# HixButton.net
KiCad netlist of a schematic drawn in EAGLE
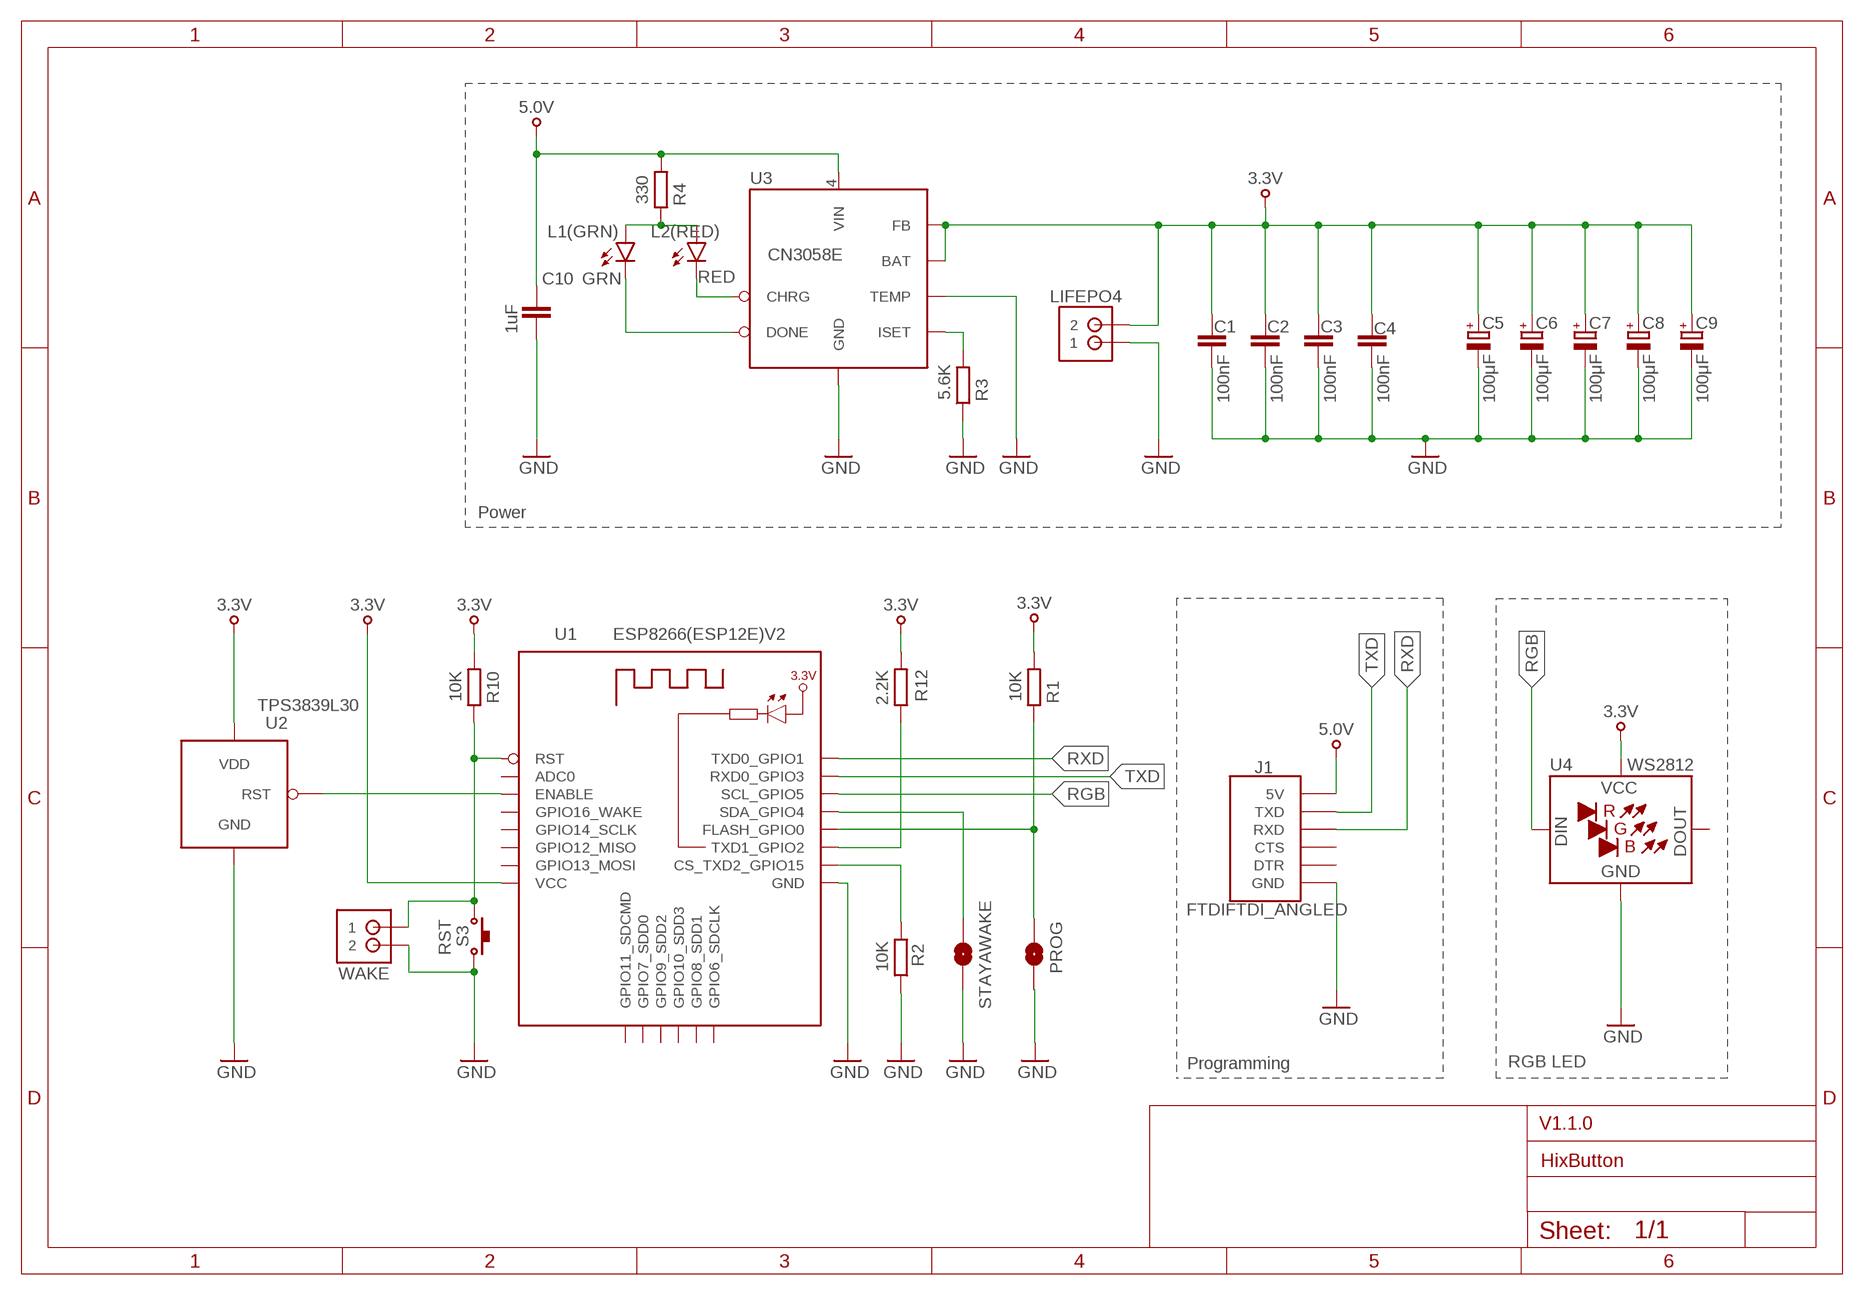
[diagram p0: schematic, sheet 1]

(export (version "E")
  (design (tool "Eeschema 10.0.6"))
  (components
    (comp (ref "C1")
      (value "100nF")
      (footprint "eagle-import:C1206")
      (libsource (lib "eagle-import") (part "C-EUC1206"))
    )
    (comp (ref "C2")
      (value "100nF")
      (footprint "eagle-import:C1206")
      (libsource (lib "eagle-import") (part "C-EUC1206"))
    )
    (comp (ref "C3")
      (value "100nF")
      (footprint "eagle-import:C1206")
      (libsource (lib "eagle-import") (part "C-EUC1206"))
    )
    (comp (ref "C4")
      (value "100nF")
      (footprint "eagle-import:C1206")
      (libsource (lib "eagle-import") (part "C-EUC1206"))
    )
    (comp (ref "C5")
      (value "100μF")
      (footprint "eagle-import:SMC_A")
      (libsource (lib "eagle-import") (part "CPOL-EUSMCA"))
    )
    (comp (ref "C6")
      (value "100μF")
      (footprint "eagle-import:SMC_A")
      (libsource (lib "eagle-import") (part "CPOL-EUSMCA"))
    )
    (comp (ref "C7")
      (value "100μF")
      (footprint "eagle-import:SMC_A")
      (libsource (lib "eagle-import") (part "CPOL-EUSMCA"))
    )
    (comp (ref "C8")
      (value "100μF")
      (footprint "eagle-import:SMC_A")
      (libsource (lib "eagle-import") (part "CPOL-EUSMCA"))
    )
    (comp (ref "C9")
      (value "100μF")
      (footprint "eagle-import:SMC_A")
      (libsource (lib "eagle-import") (part "CPOL-EUSMCA"))
    )
    (comp (ref "C10")
      (value "1uF")
      (footprint "eagle-import:C1206")
      (libsource (lib "eagle-import") (part "C-EUC1206"))
    )
    (comp (ref "J1")
      (value "FTDIFTDI_ANGLED")
      (footprint "eagle-import:FTDI_ANGLED")
      (libsource (lib "eagle-import") (part "FTDIFTDI_ANGLED"))
    )
    (comp (ref "L1(GRN)")
      (value "GRN")
      (footprint "eagle-import:CHIPLED_1206")
      (libsource (lib "eagle-import") (part "LEDCHIPLED_1206"))
    )
    (comp (ref "L2(RED)")
      (value "RED")
      (footprint "eagle-import:CHIPLED_1206")
      (libsource (lib "eagle-import") (part "LEDCHIPLED_1206"))
    )
    (comp (ref "LIFEPO4")
      (value "XH2P")
      (footprint "eagle-import:XH2P")
      (libsource (lib "eagle-import") (part "XH2P"))
    )
    (comp (ref "PROG")
      (value "SJ")
      (footprint "eagle-import:SJ")
      (fields (field (name "SPICEPREFIX") "B"))
      (libsource (lib "eagle-import") (part "SJ"))
    )
    (comp (ref "R1")
      (value "10K")
      (footprint "eagle-import:R1206")
      (libsource (lib "eagle-import") (part "R-EU_R1206"))
    )
    (comp (ref "R2")
      (value "10K")
      (footprint "eagle-import:R1206")
      (libsource (lib "eagle-import") (part "R-EU_R1206"))
    )
    (comp (ref "R3")
      (value "5.6K")
      (footprint "eagle-import:R1206")
      (libsource (lib "eagle-import") (part "R-EU_R1206"))
    )
    (comp (ref "R4")
      (value "330")
      (footprint "eagle-import:R1206")
      (libsource (lib "eagle-import") (part "R-EU_R1206"))
    )
    (comp (ref "R10")
      (value "10K")
      (footprint "eagle-import:R1206")
      (libsource (lib "eagle-import") (part "R-EU_R1206"))
    )
    (comp (ref "R12")
      (value "2.2K")
      (footprint "eagle-import:R1206")
      (libsource (lib "eagle-import") (part "R-EU_R1206"))
    )
    (comp (ref "S3")
      (value "RST")
      (footprint "eagle-import:SMDPUSHBTN_TYPE1")
      (libsource (lib "eagle-import") (part "PUSHBTNSMALL"))
    )
    (comp (ref "STAYAWAKE")
      (value "SJ")
      (footprint "eagle-import:SJ")
      (libsource (lib "eagle-import") (part "SJ"))
    )
    (comp (ref "U1")
      (value "ESP8266(ESP12E)V2")
      (footprint "eagle-import:ESP8266(ESP12E)")
      (libsource (lib "eagle-import") (part "ESP8266(ESP12E)V2"))
    )
    (comp (ref "U2")
      (value "TPS3839L30")
      (footprint "eagle-import:SOT23")
      (libsource (lib "eagle-import") (part "TPS3839"))
    )
    (comp (ref "U3")
      (value "CN3058E")
      (footprint "eagle-import:SOP8")
      (libsource (lib "eagle-import") (part "CN3058E"))
    )
    (comp (ref "U4")
      (value "WS2812")
      (footprint "eagle-import:LED_5050")
      (libsource (lib "eagle-import") (part "LED_RGBWS2812_5050"))
    )
    (comp (ref "WAKE")
      (value "XH2P")
      (footprint "eagle-import:XH2P")
      (libsource (lib "eagle-import") (part "XH2P"))
    )
  )
  (nets
    (net (code "1") (name "3.3V") (class "Default")
      (node (ref "C1") (pin "1") (pinfunction "1_1") (pintype "passive"))
      (node (ref "C2") (pin "1") (pinfunction "1_1") (pintype "passive"))
      (node (ref "C3") (pin "1") (pinfunction "1_1") (pintype "passive"))
      (node (ref "C4") (pin "1") (pinfunction "1_1") (pintype "passive"))
      (node (ref "C5") (pin "+") (pinfunction "+_+") (pintype "passive"))
      (node (ref "C6") (pin "+") (pinfunction "+_+") (pintype "passive"))
      (node (ref "C7") (pin "+") (pinfunction "+_+") (pintype "passive"))
      (node (ref "C8") (pin "+") (pinfunction "+_+") (pintype "passive"))
      (node (ref "C9") (pin "+") (pinfunction "+_+") (pintype "passive"))
      (node (ref "LIFEPO4") (pin "2") (pinfunction "2_2") (pintype "bidirectional"))
      (node (ref "R1") (pin "2") (pinfunction "2_2") (pintype "passive"))
      (node (ref "R10") (pin "2") (pinfunction "2_2") (pintype "passive"))
      (node (ref "R12") (pin "2") (pinfunction "2_2") (pintype "passive"))
      (node (ref "U1") (pin "VCC") (pinfunction "VCC_VCC") (pintype "power_in"))
      (node (ref "U2") (pin "3") (pinfunction "VDD_3") (pintype "power_in"))
      (node (ref "U3") (pin "5") (pinfunction "BAT_5") (pintype "bidirectional"))
      (node (ref "U3") (pin "8") (pinfunction "FB_8") (pintype "bidirectional"))
      (node (ref "U4") (pin "3") (pinfunction "VCC_3") (pintype "bidirectional"))
    )
    (net (code "2") (name "5.0V") (class "Default")
      (node (ref "C10") (pin "1") (pinfunction "1_1") (pintype "passive"))
      (node (ref "J1") (pin "5V") (pinfunction "5V_5V") (pintype "bidirectional"))
      (node (ref "R4") (pin "2") (pinfunction "2_2") (pintype "passive"))
      (node (ref "U3") (pin "4") (pinfunction "VIN_4") (pintype "tri_state"))
    )
    (net (code "3") (name "GND") (class "Default")
      (node (ref "C1") (pin "2") (pinfunction "2_2") (pintype "passive"))
      (node (ref "C10") (pin "2") (pinfunction "2_2") (pintype "passive"))
      (node (ref "C2") (pin "2") (pinfunction "2_2") (pintype "passive"))
      (node (ref "C3") (pin "2") (pinfunction "2_2") (pintype "passive"))
      (node (ref "C4") (pin "2") (pinfunction "2_2") (pintype "passive"))
      (node (ref "C5") (pin "-") (pinfunction "-_-") (pintype "passive"))
      (node (ref "C6") (pin "-") (pinfunction "-_-") (pintype "passive"))
      (node (ref "C7") (pin "-") (pinfunction "-_-") (pintype "passive"))
      (node (ref "C8") (pin "-") (pinfunction "-_-") (pintype "passive"))
      (node (ref "C9") (pin "-") (pinfunction "-_-") (pintype "passive"))
      (node (ref "J1") (pin "GND") (pinfunction "GND_GND") (pintype "bidirectional"))
      (node (ref "LIFEPO4") (pin "1") (pinfunction "1_1") (pintype "bidirectional"))
      (node (ref "PROG") (pin "1") (pinfunction "1_1") (pintype "passive"))
      (node (ref "R2") (pin "1") (pinfunction "1_1") (pintype "passive"))
      (node (ref "R3") (pin "1") (pinfunction "1_1") (pintype "passive"))
      (node (ref "S3") (pin "1") (pinfunction "1_1") (pintype "passive"))
      (node (ref "STAYAWAKE") (pin "1") (pinfunction "1_1") (pintype "passive"))
      (node (ref "U1") (pin "GND") (pinfunction "GND_GND") (pintype "power_in"))
      (node (ref "U2") (pin "1") (pinfunction "GND_1") (pintype "power_in"))
      (node (ref "U3") (pin "1") (pinfunction "TEMP_1") (pintype "passive"))
      (node (ref "U3") (pin "3") (pinfunction "GND_3") (pintype "power_in"))
      (node (ref "U4") (pin "1") (pinfunction "GND_1") (pintype "power_in"))
      (node (ref "WAKE") (pin "2") (pinfunction "2_2") (pintype "bidirectional"))
    )
    (net (code "4") (name "Net-(L1(GRN)-PadA)") (class "Default")
      (node (ref "L1(GRN)") (pin "A") (pinfunction "A_A") (pintype "passive"))
      (node (ref "L2(RED)") (pin "A") (pinfunction "A_A") (pintype "passive"))
      (node (ref "R4") (pin "1") (pinfunction "1_1") (pintype "passive"))
    )
    (net (code "5") (name "Net-(R10-Pad1)") (class "Default")
      (node (ref "R10") (pin "1") (pinfunction "1_1") (pintype "passive"))
      (node (ref "S3") (pin "2") (pinfunction "2_2") (pintype "passive"))
      (node (ref "U1") (pin "RST") (pinfunction "RST_RST") (pintype "input"))
      (node (ref "WAKE") (pin "1") (pinfunction "1_1") (pintype "bidirectional"))
    )
    (net (code "6") (name "Net-(U1-CS_TXD2_GPIO15)") (class "Default")
      (node (ref "R2") (pin "2") (pinfunction "2_2") (pintype "passive"))
      (node (ref "U1") (pin "GPIO15_CS_TXD2") (pinfunction "CS_TXD2_GPIO15_GPIO15_CS_TXD2") (pintype "bidirectional"))
    )
    (net (code "7") (name "Net-(U1-FLASH_GPIO0)") (class "Default")
      (node (ref "PROG") (pin "2") (pinfunction "2_2") (pintype "passive"))
      (node (ref "R1") (pin "1") (pinfunction "1_1") (pintype "passive"))
      (node (ref "U1") (pin "GPIO0_FLASH") (pinfunction "FLASH_GPIO0_GPIO0_FLASH") (pintype "bidirectional"))
    )
    (net (code "8") (name "Net-(U1-SDA_GPIO4)") (class "Default")
      (node (ref "STAYAWAKE") (pin "2") (pinfunction "2_2") (pintype "passive"))
      (node (ref "U1") (pin "GPIO4_SDA") (pinfunction "SDA_GPIO4_GPIO4_SDA") (pintype "bidirectional"))
    )
    (net (code "9") (name "Net-(U1-TXD1_GPIO2)") (class "Default")
      (node (ref "R12") (pin "1") (pinfunction "1_1") (pintype "passive"))
      (node (ref "U1") (pin "GPIO2_TXD1") (pinfunction "TXD1_GPIO2_GPIO2_TXD1") (pintype "bidirectional"))
    )
    (net (code "10") (name "Net-(U2-RST)") (class "Default")
      (node (ref "U1") (pin "ENABLE") (pinfunction "ENABLE_ENABLE") (pintype "input"))
      (node (ref "U2") (pin "2") (pinfunction "RST_2") (pintype "output"))
    )
    (net (code "11") (name "Net-(U3-CHRG)") (class "Default")
      (node (ref "L2(RED)") (pin "C") (pinfunction "C_C") (pintype "passive"))
      (node (ref "U3") (pin "7") (pinfunction "CHRG_7") (pintype "output"))
    )
    (net (code "12") (name "Net-(U3-DONE)") (class "Default")
      (node (ref "L1(GRN)") (pin "C") (pinfunction "C_C") (pintype "passive"))
      (node (ref "U3") (pin "6") (pinfunction "DONE_6") (pintype "output"))
    )
    (net (code "13") (name "Net-(U3-ISET)") (class "Default")
      (node (ref "R3") (pin "2") (pinfunction "2_2") (pintype "passive"))
      (node (ref "U3") (pin "2") (pinfunction "ISET_2") (pintype "passive"))
    )
    (net (code "14") (name "RGB") (class "Default")
      (node (ref "U1") (pin "GPIO5_SCL") (pinfunction "SCL_GPIO5_GPIO5_SCL") (pintype "bidirectional"))
      (node (ref "U4") (pin "2") (pinfunction "DIN_2") (pintype "input"))
    )
    (net (code "15") (name "RXD") (class "Default")
      (node (ref "J1") (pin "RXD") (pinfunction "RXD_RXD") (pintype "bidirectional"))
      (node (ref "U1") (pin "GPIO1_TXD0") (pinfunction "TXD0_GPIO1_GPIO1_TXD0") (pintype "bidirectional"))
    )
    (net (code "16") (name "TXD") (class "Default")
      (node (ref "J1") (pin "TXD") (pinfunction "TXD_TXD") (pintype "bidirectional"))
      (node (ref "U1") (pin "GPIO3_RXD0") (pinfunction "RXD0_GPIO3_GPIO3_RXD0") (pintype "input"))
    )
    (net (code "17") (name "unconnected-(J1-PadCTS)") (class "Default")
      (node (ref "J1") (pin "CTS") (pinfunction "CTS_CTS") (pintype "bidirectional"))
    )
    (net (code "18") (name "unconnected-(J1-PadDTR)") (class "Default")
      (node (ref "J1") (pin "DTR") (pinfunction "DTR_DTR") (pintype "bidirectional"))
    )
    (net (code "19") (name "unconnected-(U1-GPIO11_SDCMD-PadCPIO11_SDCMD)") (class "Default")
      (node (ref "U1") (pin "CPIO11_SDCMD") (pinfunction "GPIO11_SDCMD_CPIO11_SDCMD") (pintype "no_connect"))
    )
    (net (code "20") (name "unconnected-(U1-PadADC0)") (class "Default")
      (node (ref "U1") (pin "ADC0") (pinfunction "ADC0_ADC0") (pintype "input"))
    )
    (net (code "21") (name "unconnected-(U1-PadGPIO6_SDCLK)") (class "Default")
      (node (ref "U1") (pin "GPIO6_SDCLK") (pinfunction "GPIO6_SDCLK_GPIO6_SDCLK") (pintype "no_connect"))
    )
    (net (code "22") (name "unconnected-(U1-PadGPIO7_SDD0)") (class "Default")
      (node (ref "U1") (pin "GPIO7_SDD0") (pinfunction "GPIO7_SDD0_GPIO7_SDD0") (pintype "no_connect"))
    )
    (net (code "23") (name "unconnected-(U1-PadGPIO8_SDD1)") (class "Default")
      (node (ref "U1") (pin "GPIO8_SDD1") (pinfunction "GPIO8_SDD1_GPIO8_SDD1") (pintype "no_connect"))
    )
    (net (code "24") (name "unconnected-(U1-PadGPIO9_SDD2)") (class "Default")
      (node (ref "U1") (pin "GPIO9_SDD2") (pinfunction "GPIO9_SDD2_GPIO9_SDD2") (pintype "no_connect"))
    )
    (net (code "25") (name "unconnected-(U1-PadGPIO10_SDD3)") (class "Default")
      (node (ref "U1") (pin "GPIO10_SDD3") (pinfunction "GPIO10_SDD3_GPIO10_SDD3") (pintype "no_connect"))
    )
    (net (code "26") (name "unconnected-(U1-PadGPIO12_MISO)") (class "Default")
      (node (ref "U1") (pin "GPIO12_MISO") (pinfunction "GPIO12_MISO_GPIO12_MISO") (pintype "bidirectional"))
    )
    (net (code "27") (name "unconnected-(U1-PadGPIO13_MOSI)") (class "Default")
      (node (ref "U1") (pin "GPIO13_MOSI") (pinfunction "GPIO13_MOSI_GPIO13_MOSI") (pintype "bidirectional"))
    )
    (net (code "28") (name "unconnected-(U1-PadGPIO14_SCLK)") (class "Default")
      (node (ref "U1") (pin "GPIO14_SCLK") (pinfunction "GPIO14_SCLK_GPIO14_SCLK") (pintype "bidirectional"))
    )
    (net (code "29") (name "unconnected-(U1-PadGPIO16_WAKE)") (class "Default")
      (node (ref "U1") (pin "GPIO16_WAKE") (pinfunction "GPIO16_WAKE_GPIO16_WAKE") (pintype "bidirectional"))
    )
    (net (code "30") (name "unconnected-(U4-DOUT-Pad4)") (class "Default")
      (node (ref "U4") (pin "4") (pinfunction "DOUT_4") (pintype "output"))
    )
  )
)
